# TPS5450.net
KiCad netlist of a schematic drawn in Altium Designer
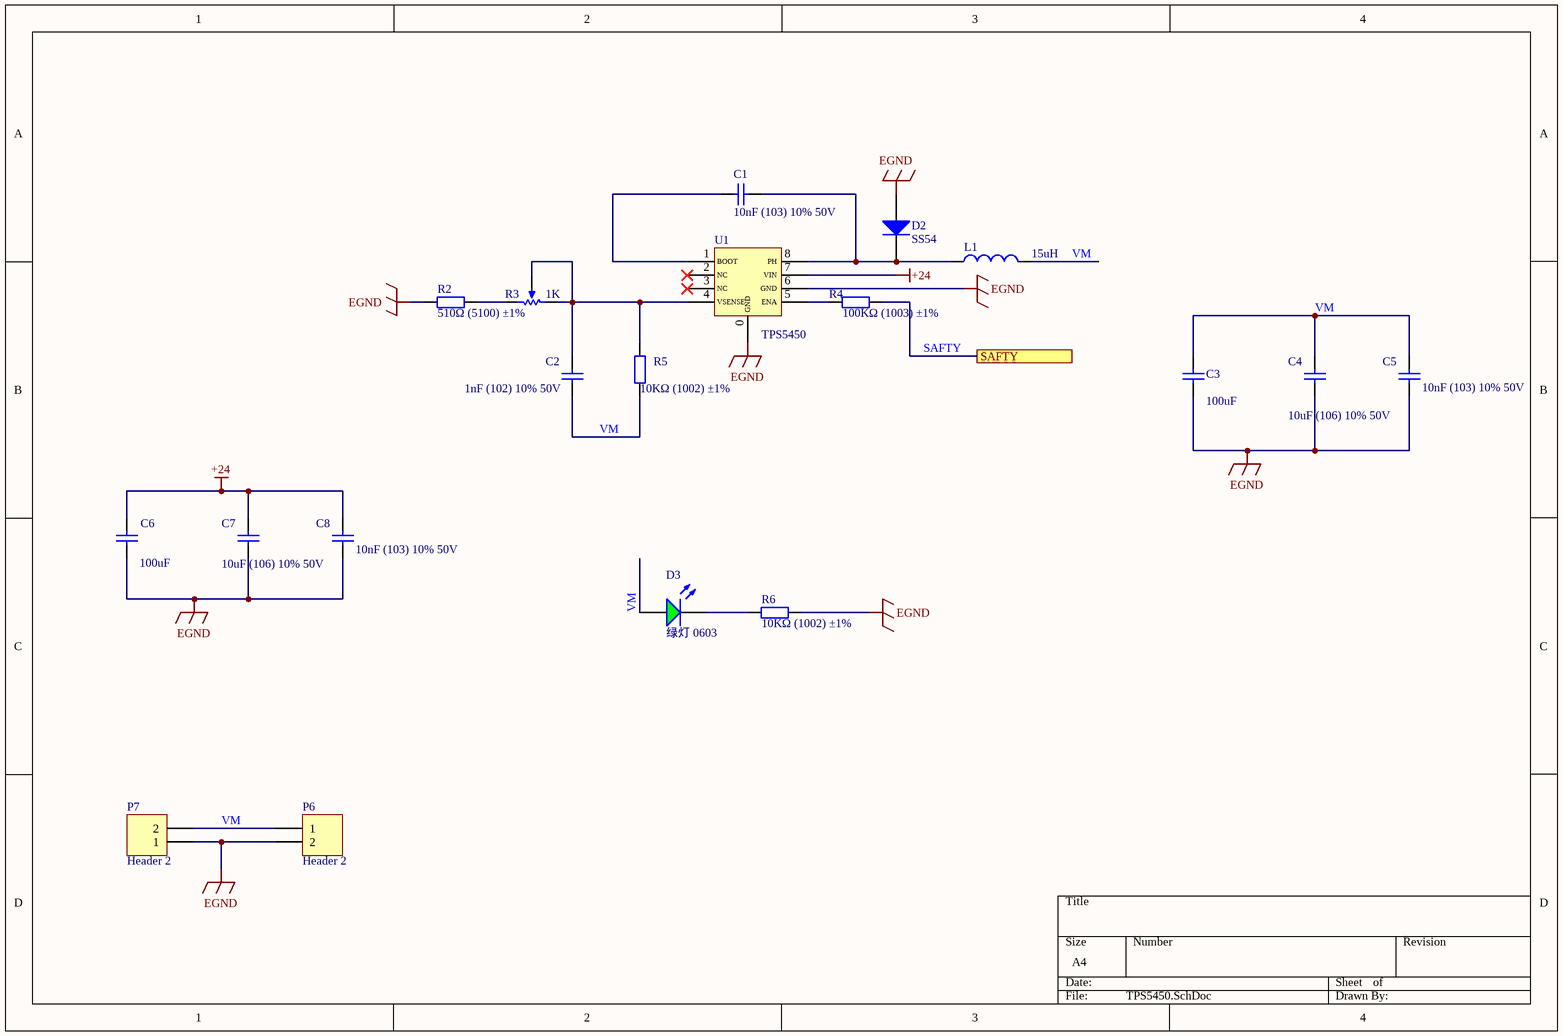
[diagram p0: TPS5450.SchDoc]

(export (version "E")
  (design (tool "Eeschema 10.0.6"))
  (components
    (comp (ref "C1")
      (value "10nF (103) 10% 50V")
      (footprint "0603_C")
      (description "贴片电容")
      (libsource (lib "Miscellaneous Devices LC") (part "0603 10nF (103) 10% 50V"))
    )
    (comp (ref "C2")
      (value "1nF (102) 10% 50V")
      (footprint "0603_C")
      (description "贴片电容")
      (libsource (lib "Miscellaneous Devices LC") (part "0603 1nF (102) 10% 50V"))
    )
    (comp (ref "C3")
      (value "100uF")
      (footprint "C100uF")
      (description "贴片电容")
      (fields (field (name "Comment") "Cap") (field (name "PUBLISHER") "Altium Limited"))
      (libsource (lib "Sparks") (part "Cap"))
    )
    (comp (ref "C4")
      (value "10uF (106) 10% 50V")
      (footprint "1206_C")
      (description "贴片电容")
      (libsource (lib "Miscellaneous Devices LC") (part "1206 10uF (106) 10% 50V"))
    )
    (comp (ref "C5")
      (value "10nF (103) 10% 50V")
      (footprint "0603_C")
      (description "贴片电容")
      (libsource (lib "Miscellaneous Devices LC") (part "0603 10nF (103) 10% 50V"))
    )
    (comp (ref "C6")
      (value "100uF")
      (footprint "C100uF")
      (description "贴片电容")
      (fields (field (name "Comment") "Cap") (field (name "PUBLISHER") "Altium Limited"))
      (libsource (lib "Sparks") (part "Cap"))
    )
    (comp (ref "C7")
      (value "10uF (106) 10% 50V")
      (footprint "1206_C")
      (description "贴片电容")
      (libsource (lib "Miscellaneous Devices LC") (part "1206 10uF (106) 10% 50V"))
    )
    (comp (ref "C8")
      (value "10nF (103) 10% 50V")
      (footprint "0603_C")
      (description "贴片电容")
      (libsource (lib "Miscellaneous Devices LC") (part "0603 10nF (103) 10% 50V"))
    )
    (comp (ref "D2")
      (value "SS54")
      (footprint "SMA(DO-214AC)_S1")
      (description "二极管")
      (libsource (lib "Diode") (part "SMA(DO-214AC) SS54"))
    )
    (comp (ref "D3")
      (value "绿灯 0603")
      (footprint "0603_LED_S1")
      (description "发光二极管")
      (libsource (lib "Miscellaneous Devices LC") (part "0603 绿灯"))
    )
    (comp (ref "L1")
      (value "15uH")
      (footprint "INDP175172X70M")
      (description "Inductor")
      (fields (field (name "PUBLISHER") "Altium Limited"))
      (libsource (lib "Miscellaneous Devices") (part "Inductor"))
    )
    (comp (ref "P6")
      (value "Header 2")
      (footprint "5.08-2P")
      (description "Header, 2-Pin")
      (fields (field (name "PUBLISHER") "Altium Limited"))
      (libsource (lib "") (part "Header 2_1"))
    )
    (comp (ref "P7")
      (value "Header 2")
      (footprint "XH-2A")
      (description "Header, 2-Pin")
      (fields (field (name "PUBLISHER") "Altium Limited"))
      (libsource (lib "Sparks") (part "Header 2"))
    )
    (comp (ref "R2")
      (value "510Ω (5100) ±1%")
      (footprint "0603_R")
      (description "贴片电阻")
      (libsource (lib "Miscellaneous Devices LC") (part "0603 510Ω (5100) 1%"))
    )
    (comp (ref "R3")
      (value "1K")
      (footprint "RP1")
      (description "电位器")
      (fields (field (name "Comment") "RPot") (field (name "PUBLISHER") "Altium Limited"))
      (libsource (lib "Sparks") (part "RPot"))
    )
    (comp (ref "R4")
      (value "100KΩ (1003) ±1%")
      (footprint "0603_R")
      (description "贴片电阻")
      (libsource (lib "Miscellaneous Devices LC") (part "0603 100KΩ (1003) 1%"))
    )
    (comp (ref "R5")
      (value "10KΩ (1002) ±1%")
      (footprint "0603_R")
      (description "贴片电阻")
      (libsource (lib "") (part "0603 10KΩ (1002) 1%_1"))
    )
    (comp (ref "R6")
      (value "10KΩ (1002) ±1%")
      (footprint "0603_R")
      (description "贴片电阻")
      (libsource (lib "Miscellaneous Devices LC") (part "0603 10KΩ (1002) 1%"))
    )
    (comp (ref "U1")
      (value "TPS5450")
      (footprint "LC-SOP-8_EP_150mil")
      (libsource (lib "2号库") (part "TPS5450"))
    )
  )
  (nets
    (net (code "1") (name "+24") (class "Default")
      (node (ref "C6") (pin "2") (pinfunction "2_2") (pintype "passive"))
      (node (ref "C7") (pin "2") (pinfunction "2_2") (pintype "passive"))
      (node (ref "C8") (pin "2") (pinfunction "2_2") (pintype "passive"))
      (node (ref "U1") (pin "7") (pinfunction "VIN_7") (pintype "passive"))
    )
    (net (code "2") (name "/SAFTY") (class "Default")
      (node (ref "R4") (pin "2") (pinfunction "2_2") (pintype "passive"))
    )
    (net (code "3") (name "/VM") (class "Default")
      (node (ref "C2") (pin "1") (pinfunction "1_1") (pintype "passive"))
      (node (ref "C3") (pin "2") (pinfunction "2_2") (pintype "passive"))
      (node (ref "C4") (pin "2") (pinfunction "2_2") (pintype "passive"))
      (node (ref "C5") (pin "2") (pinfunction "2_2") (pintype "passive"))
      (node (ref "D3") (pin "A") (pinfunction "A_A") (pintype "passive"))
      (node (ref "L1") (pin "2") (pinfunction "2_2") (pintype "passive"))
      (node (ref "P6") (pin "1") (pinfunction "1_1") (pintype "passive"))
      (node (ref "P7") (pin "2") (pinfunction "2_2") (pintype "passive"))
      (node (ref "R5") (pin "1") (pinfunction "1_1") (pintype "passive"))
    )
    (net (code "4") (name "EGND") (class "Default")
      (node (ref "C3") (pin "1") (pinfunction "1_1") (pintype "passive"))
      (node (ref "C4") (pin "1") (pinfunction "1_1") (pintype "passive"))
      (node (ref "C5") (pin "1") (pinfunction "1_1") (pintype "passive"))
      (node (ref "C6") (pin "1") (pinfunction "1_1") (pintype "passive"))
      (node (ref "C7") (pin "1") (pinfunction "1_1") (pintype "passive"))
      (node (ref "C8") (pin "1") (pinfunction "1_1") (pintype "passive"))
      (node (ref "D2") (pin "1") (pinfunction "A_1") (pintype "passive"))
      (node (ref "P6") (pin "2") (pinfunction "2_2") (pintype "passive"))
      (node (ref "P7") (pin "1") (pinfunction "1_1") (pintype "passive"))
      (node (ref "R2") (pin "1") (pinfunction "1_1") (pintype "passive"))
      (node (ref "R6") (pin "2") (pinfunction "2_2") (pintype "passive"))
      (node (ref "U1") (pin "0") (pinfunction "GND_0") (pintype "passive"))
      (node (ref "U1") (pin "6") (pinfunction "GND_6") (pintype "passive"))
    )
    (net (code "5") (name "Net-(D2-K)") (class "Default")
      (node (ref "C1") (pin "2") (pinfunction "2_2") (pintype "passive"))
      (node (ref "D2") (pin "2") (pinfunction "K_2") (pintype "passive"))
      (node (ref "L1") (pin "1") (pinfunction "1_1") (pintype "passive"))
      (node (ref "U1") (pin "8") (pinfunction "PH_8") (pintype "passive"))
    )
    (net (code "6") (name "Net-(D3-PadK)") (class "Default")
      (node (ref "D3") (pin "K") (pinfunction "K_K") (pintype "passive"))
      (node (ref "R6") (pin "1") (pinfunction "1_1") (pintype "passive"))
    )
    (net (code "7") (name "Net-(R3-BOT)") (class "Default")
      (node (ref "C2") (pin "2") (pinfunction "2_2") (pintype "passive"))
      (node (ref "R3") (pin "2") (pinfunction "TAP_2") (pintype "passive"))
      (node (ref "R3") (pin "3") (pinfunction "BOT_3") (pintype "passive"))
      (node (ref "R5") (pin "2") (pinfunction "2_2") (pintype "passive"))
      (node (ref "U1") (pin "4") (pinfunction "VSENSE_4") (pintype "passive"))
    )
    (net (code "8") (name "Net-(R3-TOP)") (class "Default")
      (node (ref "R2") (pin "2") (pinfunction "2_2") (pintype "passive"))
      (node (ref "R3") (pin "1") (pinfunction "TOP_1") (pintype "passive"))
    )
    (net (code "9") (name "Net-(U1-BOOT)") (class "Default")
      (node (ref "C1") (pin "1") (pinfunction "1_1") (pintype "passive"))
      (node (ref "U1") (pin "1") (pinfunction "BOOT_1") (pintype "passive"))
    )
    (net (code "10") (name "Net-(U1-ENA)") (class "Default")
      (node (ref "R4") (pin "1") (pinfunction "1_1") (pintype "passive"))
      (node (ref "U1") (pin "5") (pinfunction "ENA_5") (pintype "passive"))
    )
    (net (code "11") (name "unconnected-(U1-NC-Pad2)") (class "Default")
      (node (ref "U1") (pin "2") (pinfunction "NC_2") (pintype "passive+no_connect"))
    )
    (net (code "12") (name "unconnected-(U1-NC-Pad3)") (class "Default")
      (node (ref "U1") (pin "3") (pinfunction "NC_3") (pintype "passive+no_connect"))
    )
  )
)
